# main_gyro_acc_only.net
KiCad netlist of a schematic drawn in Altium Designer
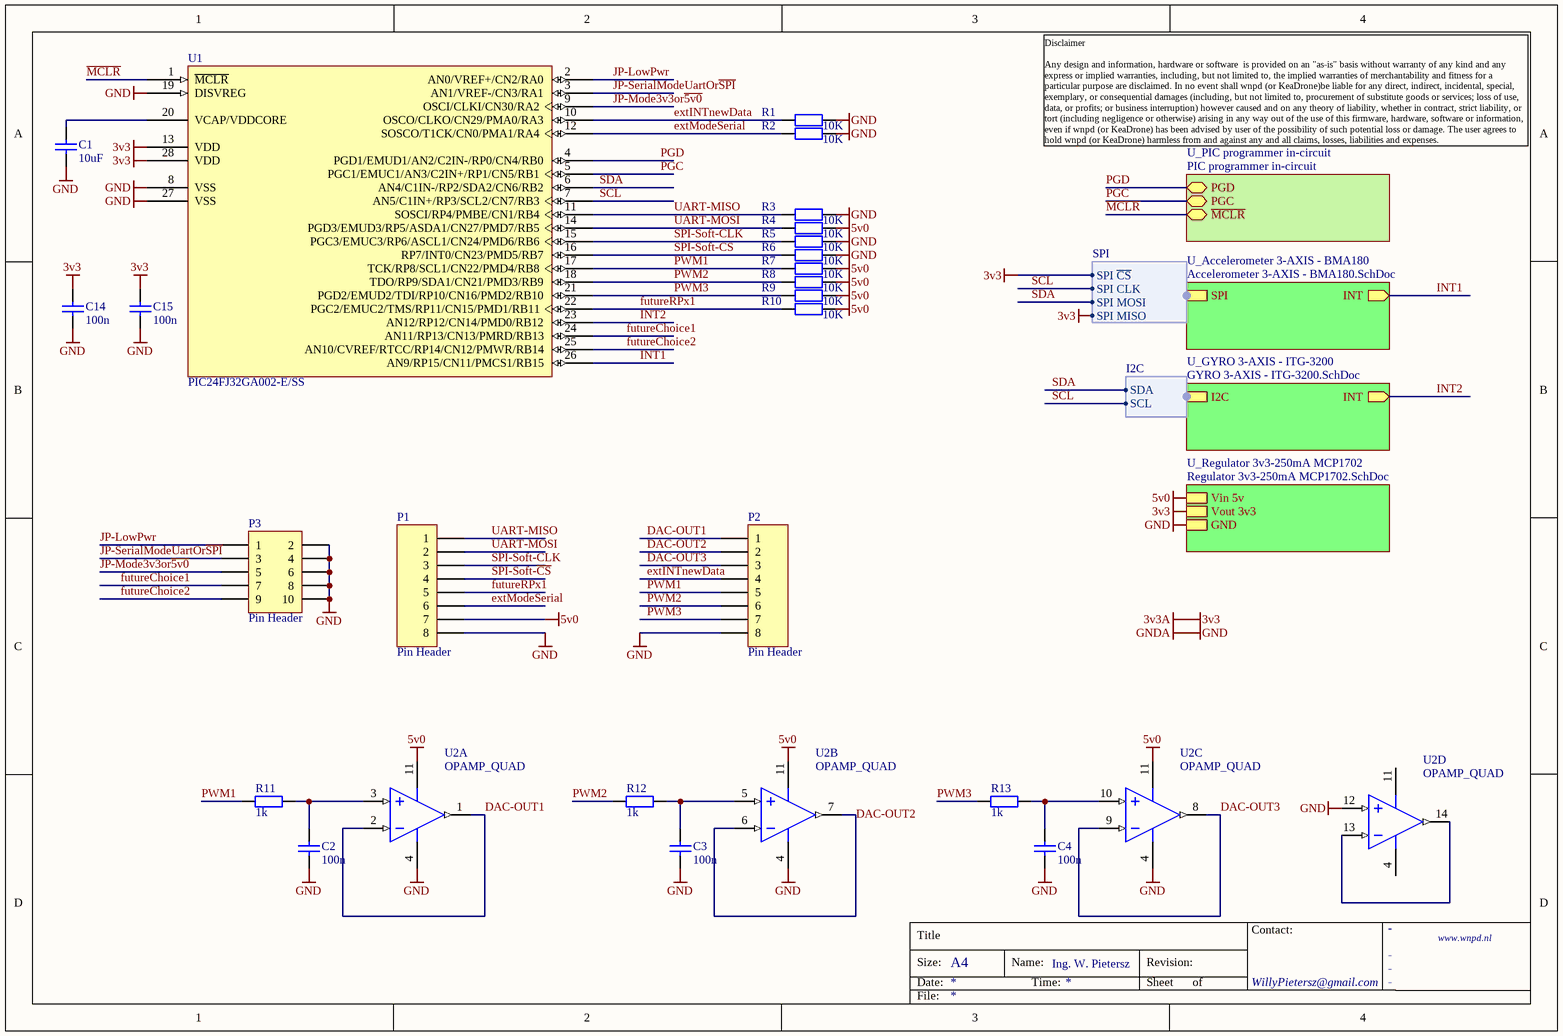
[diagram p0: main_gyro+acc only.SchDoc]

(export (version "E")
  (design (tool "Eeschema 10.0.6"))
  (components
    (comp (ref "C1")
      (value "10uF")
      (footprint "C1206")
      (fields
        (field (name "VOLTAGE") "10V")
        (field (name "TOLERANCE") "0.1")
        (field (name "AUTHOR") "Willem Pietersz")
      )
      (libsource (lib "OurDb") (part "cap_NonPolar"))
    )
    (comp (ref "C2")
      (value "100n")
      (footprint "C0805")
      (fields (field (name "TOLERANCE") "0.1") (field (name "AUTHOR") "Willy Pietersz"))
      (libsource (lib "OurDb") (part "cap_NonPolar"))
    )
    (comp (ref "C3")
      (value "100n")
      (footprint "C0805")
      (fields (field (name "TOLERANCE") "0.1") (field (name "AUTHOR") "Willy Pietersz"))
      (libsource (lib "OurDb") (part "cap_NonPolar"))
    )
    (comp (ref "C4")
      (value "100n")
      (footprint "C0805")
      (fields (field (name "TOLERANCE") "0.1") (field (name "AUTHOR") "Willy Pietersz"))
      (libsource (lib "OurDb") (part "cap_NonPolar"))
    )
    (comp (ref "C14")
      (value "100n")
      (footprint "C0805")
      (fields (field (name "TOLERANCE") "0.1") (field (name "AUTHOR") "Willy Pietersz"))
      (libsource (lib "OurDb") (part "cap_NonPolar"))
    )
    (comp (ref "C15")
      (value "100n")
      (footprint "C0805")
      (fields (field (name "TOLERANCE") "0.1") (field (name "AUTHOR") "Willy Pietersz"))
      (libsource (lib "OurDb") (part "cap_NonPolar"))
    )
    (comp (ref "P1")
      (value "Pin Header")
      (footprint "PH1x8_2.54")
      (description "Con1x8")
      (fields (field (name "PART NUMBER") "PH1x8") (field (name "AUTHOR") "Willy Pietersz"))
      (libsource (lib "") (part "Con1x8_1"))
    )
    (comp (ref "P2")
      (value "Pin Header")
      (footprint "PH1x8_2.54")
      (description "Con1x8")
      (fields (field (name "PART NUMBER") "PH1x8") (field (name "AUTHOR") "Willy Pietersz"))
      (libsource (lib "OurDb") (part "Con1x8"))
    )
    (comp (ref "P3")
      (value "Pin Header")
      (footprint "PH2x5_2.54")
      (description "Header, 5-Pin, Dual row")
      (fields (field (name "PART NUMBER") "PH2x5") (field (name "AUTHOR") "Willy Pietersz"))
      (libsource (lib "OurDb") (part "Con2x5"))
    )
    (comp (ref "R1")
      (value "10K")
      (footprint "R0805")
      (description "Resistor")
      (fields
        (field (name "POWER") "0.25W")
        (field (name "TOLERANCE") "0.05")
        (field (name "PUBLISHER") "Altium Limited")
        (field (name "AUTHOR") "Willy Pietersz")
      )
      (libsource (lib "OurDb") (part "RESISTOR"))
    )
    (comp (ref "R2")
      (value "10K")
      (footprint "R0805")
      (description "Resistor")
      (fields
        (field (name "POWER") "0.25W")
        (field (name "TOLERANCE") "0.05")
        (field (name "PUBLISHER") "Altium Limited")
        (field (name "AUTHOR") "Willy Pietersz")
      )
      (libsource (lib "OurDb") (part "RESISTOR"))
    )
    (comp (ref "R3")
      (value "10K")
      (footprint "R0805")
      (description "Resistor")
      (fields
        (field (name "POWER") "0.25W")
        (field (name "TOLERANCE") "0.05")
        (field (name "PUBLISHER") "Altium Limited")
        (field (name "AUTHOR") "Willy Pietersz")
      )
      (libsource (lib "OurDb") (part "RESISTOR"))
    )
    (comp (ref "R4")
      (value "10K")
      (footprint "R0805")
      (description "Resistor")
      (fields
        (field (name "POWER") "0.25W")
        (field (name "TOLERANCE") "0.05")
        (field (name "PUBLISHER") "Altium Limited")
        (field (name "AUTHOR") "Willy Pietersz")
      )
      (libsource (lib "OurDb") (part "RESISTOR"))
    )
    (comp (ref "R5")
      (value "10K")
      (footprint "R0805")
      (description "Resistor")
      (fields
        (field (name "POWER") "0.25W")
        (field (name "TOLERANCE") "0.05")
        (field (name "PUBLISHER") "Altium Limited")
        (field (name "AUTHOR") "Willy Pietersz")
      )
      (libsource (lib "OurDb") (part "RESISTOR"))
    )
    (comp (ref "R6")
      (value "10K")
      (footprint "R0805")
      (description "Resistor")
      (fields
        (field (name "POWER") "0.25W")
        (field (name "TOLERANCE") "0.05")
        (field (name "PUBLISHER") "Altium Limited")
        (field (name "AUTHOR") "Willy Pietersz")
      )
      (libsource (lib "OurDb") (part "RESISTOR"))
    )
    (comp (ref "R7")
      (value "10K")
      (footprint "R0805")
      (description "Resistor")
      (fields
        (field (name "POWER") "0.25W")
        (field (name "TOLERANCE") "0.05")
        (field (name "PUBLISHER") "Altium Limited")
        (field (name "AUTHOR") "Willy Pietersz")
      )
      (libsource (lib "OurDb") (part "RESISTOR"))
    )
    (comp (ref "R8")
      (value "10K")
      (footprint "R0805")
      (description "Resistor")
      (fields
        (field (name "POWER") "0.25W")
        (field (name "TOLERANCE") "0.05")
        (field (name "PUBLISHER") "Altium Limited")
        (field (name "AUTHOR") "Willy Pietersz")
      )
      (libsource (lib "OurDb") (part "RESISTOR"))
    )
    (comp (ref "R9")
      (value "10K")
      (footprint "R0805")
      (description "Resistor")
      (fields
        (field (name "POWER") "0.25W")
        (field (name "TOLERANCE") "0.05")
        (field (name "PUBLISHER") "Altium Limited")
        (field (name "AUTHOR") "Willy Pietersz")
      )
      (libsource (lib "OurDb") (part "RESISTOR"))
    )
    (comp (ref "R10")
      (value "10K")
      (footprint "R0805")
      (description "Resistor")
      (fields
        (field (name "POWER") "0.25W")
        (field (name "TOLERANCE") "0.05")
        (field (name "PUBLISHER") "Altium Limited")
        (field (name "AUTHOR") "Willy Pietersz")
      )
      (libsource (lib "OurDb") (part "RESISTOR"))
    )
    (comp (ref "R11")
      (value "1k")
      (footprint "R0805")
      (description "Resistor")
      (fields
        (field (name "PART NUMBER") "1K")
        (field (name "POWER") "0.25W")
        (field (name "PUBLISHER") "Altium Limited")
        (field (name "AUTHOR") "Willy Pietersz")
      )
      (libsource (lib "OurDb") (part "RESISTOR"))
    )
    (comp (ref "R12")
      (value "1k")
      (footprint "R0805")
      (description "Resistor")
      (fields
        (field (name "PART NUMBER") "1K")
        (field (name "POWER") "0.25W")
        (field (name "PUBLISHER") "Altium Limited")
        (field (name "AUTHOR") "Willy Pietersz")
      )
      (libsource (lib "OurDb") (part "RESISTOR"))
    )
    (comp (ref "R13")
      (value "1k")
      (footprint "R0805")
      (description "Resistor")
      (fields
        (field (name "PART NUMBER") "1K")
        (field (name "POWER") "0.25W")
        (field (name "PUBLISHER") "Altium Limited")
        (field (name "AUTHOR") "Willy Pietersz")
      )
      (libsource (lib "OurDb") (part "RESISTOR"))
    )
    (comp (ref "U1")
      (value "PIC24FJ32GA002-E/SS")
      (footprint "SSOP-SS28_N")
      (fields (field (name "PUBLISHER") "Altium Limited"))
      (libsource (lib "Microchip Microcontroller 16-Bit PIC24F") (part "PIC24FJ32GA002-E/SS"))
    )
    (comp (ref "U2")
      (value "OPAMP_QUAD")
      (footprint "SOIC-14")
      (description "OpAmp")
      (fields (field (name "PART NUMBER") "MCP6244-E/SN") (field (name "AUTHOR") "Willem Pietersz"))
      (libsource (lib "OurDb") (part "OPAMP_QUAD"))
    )
  )
  (nets
    (net (code "1") (name "/DAC-OUT1") (class "Default")
      (node (ref "P2") (pin "1") (pinfunction "1_1") (pintype "passive"))
      (node (ref "U2") (pin "1") (pinfunction "VOUTA_1") (pintype "output"))
      (node (ref "U2") (pin "2") (pinfunction "VINA-_2") (pintype "input"))
    )
    (net (code "2") (name "/DAC-OUT2") (class "Default")
      (node (ref "P2") (pin "2") (pinfunction "2_2") (pintype "passive"))
      (node (ref "U2") (pin "6") (pinfunction "VINB-_6") (pintype "input"))
      (node (ref "U2") (pin "7") (pinfunction "VOUTB_7") (pintype "output"))
    )
    (net (code "3") (name "/DAC-OUT3") (class "Default")
      (node (ref "P2") (pin "3") (pinfunction "3_3") (pintype "passive"))
      (node (ref "U2") (pin "8") (pinfunction "VOUTC_8") (pintype "output"))
      (node (ref "U2") (pin "9") (pinfunction "VINC-_9") (pintype "input"))
    )
    (net (code "5") (name "/INT1") (class "Default")
      (node (ref "U1") (pin "26") (pinfunction "AN9/RP15/CN11/PMCS1/RB15_26") (pintype "bidirectional"))
    )
    (net (code "6") (name "/INT2") (class "Default")
      (node (ref "U1") (pin "23") (pinfunction "AN12/RP12/CN14/PMD0/RB12_23") (pintype "bidirectional"))
    )
    (net (code "7") (name "/JP-LowPwr") (class "Default")
      (node (ref "P3") (pin "1") (pinfunction "1_1") (pintype "passive"))
      (node (ref "U1") (pin "2") (pinfunction "AN0/VREF+/CN2/RA0_2") (pintype "bidirectional"))
    )
    (net (code "8") (name "/JP-Mode3v3or~{5v0}") (class "Default")
      (node (ref "P3") (pin "5") (pinfunction "5_5") (pintype "passive"))
      (node (ref "U1") (pin "9") (pinfunction "OSCI/CLKI/CN30/RA2_9") (pintype "bidirectional"))
    )
    (net (code "9") (name "/JP-SerialModeUartOr~{SPI}") (class "Default")
      (node (ref "P3") (pin "3") (pinfunction "3_3") (pintype "passive"))
      (node (ref "U1") (pin "3") (pinfunction "AN1/VREF-/CN3/RA1_3") (pintype "bidirectional"))
    )
    (net (code "10") (name "/PGC") (class "Default")
      (node (ref "U1") (pin "5") (pinfunction "PGC1/EMUC1/AN3/C2IN+/RP1/CN5/RB1_5") (pintype "bidirectional"))
    )
    (net (code "11") (name "/PGD") (class "Default")
      (node (ref "U1") (pin "4") (pinfunction "PGD1/EMUD1/AN2/C2IN-/RP0/CN4/RB0_4") (pintype "bidirectional"))
    )
    (net (code "12") (name "/PWM1") (class "Default")
      (node (ref "P2") (pin "5") (pinfunction "5_5") (pintype "passive"))
      (node (ref "R11") (pin "2") (pinfunction "2_2") (pintype "passive"))
      (node (ref "R7") (pin "2") (pinfunction "2_2") (pintype "passive"))
      (node (ref "U1") (pin "17") (pinfunction "TCK/RP8/SCL1/CN22/PMD4/RB8_17") (pintype "bidirectional"))
    )
    (net (code "13") (name "/PWM2") (class "Default")
      (node (ref "P2") (pin "6") (pinfunction "6_6") (pintype "passive"))
      (node (ref "R12") (pin "2") (pinfunction "2_2") (pintype "passive"))
      (node (ref "R8") (pin "2") (pinfunction "2_2") (pintype "passive"))
      (node (ref "U1") (pin "18") (pinfunction "TDO/RP9/SDA1/CN21/PMD3/RB9_18") (pintype "bidirectional"))
    )
    (net (code "14") (name "/PWM3") (class "Default")
      (node (ref "P2") (pin "7") (pinfunction "7_7") (pintype "passive"))
      (node (ref "R13") (pin "2") (pinfunction "2_2") (pintype "passive"))
      (node (ref "R9") (pin "2") (pinfunction "2_2") (pintype "passive"))
      (node (ref "U1") (pin "21") (pinfunction "PGD2/EMUD2/TDI/RP10/CN16/PMD2/RB10_21") (pintype "bidirectional"))
    )
    (net (code "15") (name "/SCL") (class "Default")
      (node (ref "U1") (pin "7") (pinfunction "AN5/C1IN+/RP3/SCL2/CN7/RB3_7") (pintype "bidirectional"))
    )
    (net (code "16") (name "/SDA") (class "Default")
      (node (ref "U1") (pin "6") (pinfunction "AN4/C1IN-/RP2/SDA2/CN6/RB2_6") (pintype "bidirectional"))
    )
    (net (code "17") (name "/SPI-Soft-CLK") (class "Default")
      (node (ref "P1") (pin "3") (pinfunction "3_3") (pintype "passive"))
      (node (ref "R5") (pin "2") (pinfunction "2_2") (pintype "passive"))
      (node (ref "U1") (pin "15") (pinfunction "PGC3/EMUC3/RP6/ASCL1/CN24/PMD6/RB6_15") (pintype "bidirectional"))
    )
    (net (code "18") (name "/SPI-Soft-~{CS}") (class "Default")
      (node (ref "P1") (pin "4") (pinfunction "4_4") (pintype "passive"))
      (node (ref "R6") (pin "2") (pinfunction "2_2") (pintype "passive"))
      (node (ref "U1") (pin "16") (pinfunction "RP7/INT0/CN23/PMD5/RB7_16") (pintype "bidirectional"))
    )
    (net (code "20") (name "/UART-MISO") (class "Default")
      (node (ref "P1") (pin "1") (pinfunction "1_1") (pintype "passive"))
      (node (ref "R3") (pin "2") (pinfunction "2_2") (pintype "passive"))
      (node (ref "U1") (pin "11") (pinfunction "SOSCI/RP4/PMBE/CN1/RB4_11") (pintype "bidirectional"))
    )
    (net (code "21") (name "/UART-MOSI") (class "Default")
      (node (ref "P1") (pin "2") (pinfunction "2_2") (pintype "passive"))
      (node (ref "R4") (pin "2") (pinfunction "2_2") (pintype "passive"))
      (node (ref "U1") (pin "14") (pinfunction "PGD3/EMUD3/RP5/ASDA1/CN27/PMD7/RB5_14") (pintype "bidirectional"))
    )
    (net (code "22") (name "/extINTnewData") (class "Default")
      (node (ref "P2") (pin "4") (pinfunction "4_4") (pintype "passive"))
      (node (ref "R1") (pin "2") (pinfunction "2_2") (pintype "passive"))
      (node (ref "U1") (pin "10") (pinfunction "OSCO/CLKO/CN29/PMA0/RA3_10") (pintype "bidirectional"))
    )
    (net (code "23") (name "/extModeSerial") (class "Default")
      (node (ref "P1") (pin "6") (pinfunction "6_6") (pintype "passive"))
      (node (ref "R2") (pin "2") (pinfunction "2_2") (pintype "passive"))
      (node (ref "U1") (pin "12") (pinfunction "SOSCO/T1CK/CN0/PMA1/RA4_12") (pintype "bidirectional"))
    )
    (net (code "24") (name "/futureChoice1") (class "Default")
      (node (ref "P3") (pin "7") (pinfunction "7_7") (pintype "passive"))
      (node (ref "U1") (pin "24") (pinfunction "AN11/RP13/CN13/PMRD/RB13_24") (pintype "bidirectional"))
    )
    (net (code "25") (name "/futureChoice2") (class "Default")
      (node (ref "P3") (pin "9") (pinfunction "9_9") (pintype "passive"))
      (node (ref "U1") (pin "25") (pinfunction "AN10/CVREF/RTCC/RP14/CN12/PMWR/RB14_25") (pintype "bidirectional"))
    )
    (net (code "26") (name "/futureRPx1") (class "Default")
      (node (ref "P1") (pin "5") (pinfunction "5_5") (pintype "passive"))
      (node (ref "R10") (pin "2") (pinfunction "2_2") (pintype "passive"))
      (node (ref "U1") (pin "22") (pinfunction "PGC2/EMUC2/TMS/RP11/CN15/PMD1/RB11_22") (pintype "bidirectional"))
    )
    (net (code "27") (name "/~{MCLR}") (class "Default")
      (node (ref "U1") (pin "1") (pinfunction "~{MCLR}_1") (pintype "input"))
    )
    (net (code "28") (name "3v3") (class "Default")
      (node (ref "C14") (pin "2") (pinfunction "2_2") (pintype "passive"))
      (node (ref "C15") (pin "2") (pinfunction "2_2") (pintype "passive"))
      (node (ref "U1") (pin "13") (pinfunction "VDD_13") (pintype "power_in"))
      (node (ref "U1") (pin "28") (pinfunction "VDD_28") (pintype "power_in"))
    )
    (net (code "29") (name "5v0") (class "Default")
      (node (ref "P1") (pin "7") (pinfunction "7_7") (pintype "passive"))
      (node (ref "R10") (pin "1") (pinfunction "1_1") (pintype "passive"))
      (node (ref "R4") (pin "1") (pinfunction "1_1") (pintype "passive"))
      (node (ref "R7") (pin "1") (pinfunction "1_1") (pintype "passive"))
      (node (ref "R8") (pin "1") (pinfunction "1_1") (pintype "passive"))
      (node (ref "R9") (pin "1") (pinfunction "1_1") (pintype "passive"))
      (node (ref "U2") (pin "11") (pinfunction "VSS_11") (pintype "power_in"))
    )
    (net (code "30") (name "GND") (class "Default")
      (node (ref "C1") (pin "1") (pinfunction "1_1") (pintype "passive"))
      (node (ref "C14") (pin "1") (pinfunction "1_1") (pintype "passive"))
      (node (ref "C15") (pin "1") (pinfunction "1_1") (pintype "passive"))
      (node (ref "C2") (pin "1") (pinfunction "1_1") (pintype "passive"))
      (node (ref "C3") (pin "1") (pinfunction "1_1") (pintype "passive"))
      (node (ref "C4") (pin "1") (pinfunction "1_1") (pintype "passive"))
      (node (ref "P1") (pin "8") (pinfunction "8_8") (pintype "passive"))
      (node (ref "P2") (pin "8") (pinfunction "8_8") (pintype "passive"))
      (node (ref "P3") (pin "10") (pinfunction "10_10") (pintype "passive"))
      (node (ref "P3") (pin "2") (pinfunction "2_2") (pintype "passive"))
      (node (ref "P3") (pin "4") (pinfunction "4_4") (pintype "passive"))
      (node (ref "P3") (pin "6") (pinfunction "6_6") (pintype "passive"))
      (node (ref "P3") (pin "8") (pinfunction "8_8") (pintype "passive"))
      (node (ref "R1") (pin "1") (pinfunction "1_1") (pintype "passive"))
      (node (ref "R2") (pin "1") (pinfunction "1_1") (pintype "passive"))
      (node (ref "R3") (pin "1") (pinfunction "1_1") (pintype "passive"))
      (node (ref "R5") (pin "1") (pinfunction "1_1") (pintype "passive"))
      (node (ref "R6") (pin "1") (pinfunction "1_1") (pintype "passive"))
      (node (ref "U1") (pin "19") (pinfunction "DISVREG_19") (pintype "input"))
      (node (ref "U1") (pin "27") (pinfunction "VSS_27") (pintype "power_in"))
      (node (ref "U1") (pin "8") (pinfunction "VSS_8") (pintype "power_in"))
      (node (ref "U2") (pin "12") (pinfunction "VIND+_12") (pintype "input"))
      (node (ref "U2") (pin "4") (pinfunction "VDD_4") (pintype "power_in"))
    )
    (net (code "31") (name "Net-(U1-VCAP{slash}VDDCORE)") (class "Default")
      (node (ref "C1") (pin "2") (pinfunction "2_2") (pintype "passive"))
      (node (ref "U1") (pin "20") (pinfunction "VCAP/VDDCORE_20") (pintype "power_in"))
    )
    (net (code "32") (name "Net-(U2A-VINA+)") (class "Default")
      (node (ref "C2") (pin "2") (pinfunction "2_2") (pintype "passive"))
      (node (ref "R11") (pin "1") (pinfunction "1_1") (pintype "passive"))
      (node (ref "U2") (pin "3") (pinfunction "VINA+_3") (pintype "input"))
    )
    (net (code "33") (name "Net-(U2B-VINB+)") (class "Default")
      (node (ref "C3") (pin "2") (pinfunction "2_2") (pintype "passive"))
      (node (ref "R12") (pin "1") (pinfunction "1_1") (pintype "passive"))
      (node (ref "U2") (pin "5") (pinfunction "VINB+_5") (pintype "input"))
    )
    (net (code "34") (name "Net-(U2C-VINC+)") (class "Default")
      (node (ref "C4") (pin "2") (pinfunction "2_2") (pintype "passive"))
      (node (ref "R13") (pin "1") (pinfunction "1_1") (pintype "passive"))
      (node (ref "U2") (pin "10") (pinfunction "VINC+_10") (pintype "input"))
    )
    (net (code "35") (name "Net-(U2D-VIND-)") (class "Default")
      (node (ref "U2") (pin "13") (pinfunction "VIND-_13") (pintype "input"))
      (node (ref "U2") (pin "14") (pinfunction "VOUTD_14") (pintype "output"))
    )
    (net (code "36") (name "unconnected-(U2D-VDD-Pad4)") (class "Default")
      (node (ref "U2") (pin "4") (pinfunction "VDD_4") (pintype "power_in"))
    )
    (net (code "37") (name "unconnected-(U2D-VSS-Pad11)") (class "Default")
      (node (ref "U2") (pin "11") (pinfunction "VSS_11") (pintype "power_in"))
    )
  )
)
